# LAD_1_1.net
KiCad netlist of a schematic drawn in EAGLE
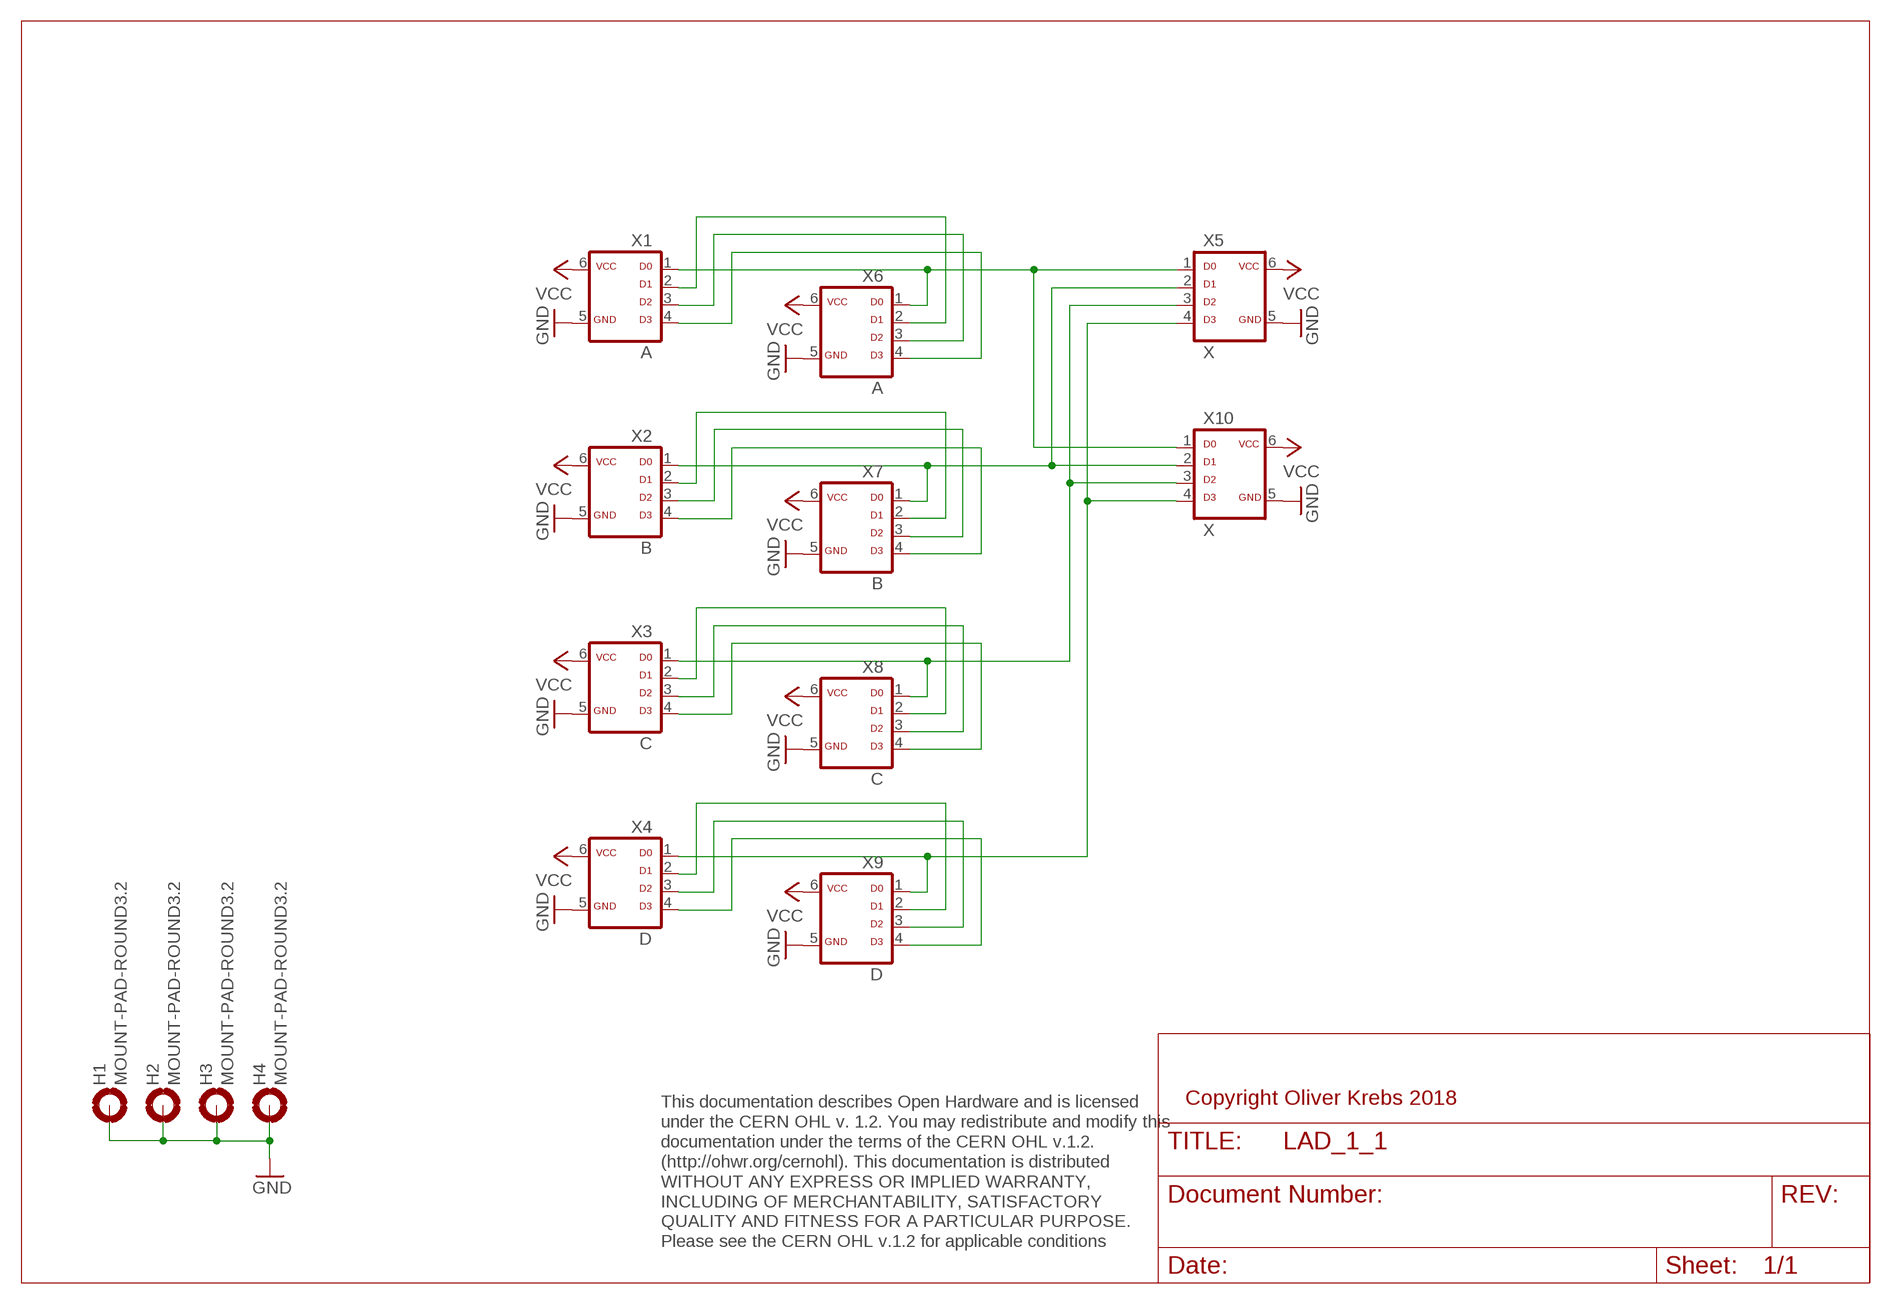
[diagram p0: schematic, sheet 1]

(export (version "E")
  (design (tool "Eeschema 10.0.6"))
  (components
    (comp (ref "H1")
      (value "MOUNT-PAD-ROUND3.2")
      (footprint "eagle-import:3,2-PAD")
      (libsource (lib "eagle-import") (part "MOUNT-PAD-ROUND3.2"))
    )
    (comp (ref "H2")
      (value "MOUNT-PAD-ROUND3.2")
      (footprint "eagle-import:3,2-PAD")
      (libsource (lib "eagle-import") (part "MOUNT-PAD-ROUND3.2"))
    )
    (comp (ref "H3")
      (value "MOUNT-PAD-ROUND3.2")
      (footprint "eagle-import:3,2-PAD")
      (libsource (lib "eagle-import") (part "MOUNT-PAD-ROUND3.2"))
    )
    (comp (ref "H4")
      (value "MOUNT-PAD-ROUND3.2")
      (footprint "eagle-import:3,2-PAD")
      (libsource (lib "eagle-import") (part "MOUNT-PAD-ROUND3.2"))
    )
    (comp (ref "X1")
      (value "A")
      (footprint "eagle-import:ML-6")
      (libsource (lib "eagle-import") (part "ML6D"))
    )
    (comp (ref "X2")
      (value "B")
      (footprint "eagle-import:ML-6")
      (libsource (lib "eagle-import") (part "ML6D"))
    )
    (comp (ref "X3")
      (value "C")
      (footprint "eagle-import:ML-6")
      (libsource (lib "eagle-import") (part "ML6D"))
    )
    (comp (ref "X4")
      (value "D")
      (footprint "eagle-import:ML-6")
      (libsource (lib "eagle-import") (part "ML6D"))
    )
    (comp (ref "X5")
      (value "X")
      (footprint "eagle-import:ML-6")
      (libsource (lib "eagle-import") (part "ML6D"))
    )
    (comp (ref "X6")
      (value "A")
      (footprint "eagle-import:ML-6")
      (libsource (lib "eagle-import") (part "ML6D"))
    )
    (comp (ref "X7")
      (value "B")
      (footprint "eagle-import:ML-6")
      (libsource (lib "eagle-import") (part "ML6D"))
    )
    (comp (ref "X8")
      (value "C")
      (footprint "eagle-import:ML-6")
      (libsource (lib "eagle-import") (part "ML6D"))
    )
    (comp (ref "X9")
      (value "D")
      (footprint "eagle-import:ML-6")
      (libsource (lib "eagle-import") (part "ML6D"))
    )
    (comp (ref "X10")
      (value "X")
      (footprint "eagle-import:ML-6")
      (libsource (lib "eagle-import") (part "ML6D"))
    )
  )
  (nets
    (net (code "1") (name "GND") (class "Default")
      (node (ref "H1") (pin "B3,2") (pinfunction "MOUNT_B3,2") (pintype "passive"))
      (node (ref "H2") (pin "B3,2") (pinfunction "MOUNT_B3,2") (pintype "passive"))
      (node (ref "H3") (pin "B3,2") (pinfunction "MOUNT_B3,2") (pintype "passive"))
      (node (ref "H4") (pin "B3,2") (pinfunction "MOUNT_B3,2") (pintype "passive"))
      (node (ref "X1") (pin "5") (pinfunction "5_5") (pintype "passive"))
      (node (ref "X10") (pin "5") (pinfunction "5_5") (pintype "passive"))
      (node (ref "X2") (pin "5") (pinfunction "5_5") (pintype "passive"))
      (node (ref "X3") (pin "5") (pinfunction "5_5") (pintype "passive"))
      (node (ref "X4") (pin "5") (pinfunction "5_5") (pintype "passive"))
      (node (ref "X5") (pin "5") (pinfunction "5_5") (pintype "passive"))
      (node (ref "X6") (pin "5") (pinfunction "5_5") (pintype "passive"))
      (node (ref "X7") (pin "5") (pinfunction "5_5") (pintype "passive"))
      (node (ref "X8") (pin "5") (pinfunction "5_5") (pintype "passive"))
      (node (ref "X9") (pin "5") (pinfunction "5_5") (pintype "passive"))
    )
    (net (code "2") (name "Net-(X1-Pad1)") (class "Default")
      (node (ref "X1") (pin "1") (pinfunction "1_1") (pintype "passive"))
      (node (ref "X10") (pin "1") (pinfunction "1_1") (pintype "passive"))
      (node (ref "X5") (pin "1") (pinfunction "1_1") (pintype "passive"))
      (node (ref "X6") (pin "1") (pinfunction "1_1") (pintype "passive"))
    )
    (net (code "3") (name "Net-(X1-Pad2)") (class "Default")
      (node (ref "X1") (pin "2") (pinfunction "2_2") (pintype "passive"))
      (node (ref "X6") (pin "2") (pinfunction "2_2") (pintype "passive"))
    )
    (net (code "4") (name "Net-(X1-Pad3)") (class "Default")
      (node (ref "X1") (pin "3") (pinfunction "3_3") (pintype "passive"))
      (node (ref "X6") (pin "3") (pinfunction "3_3") (pintype "passive"))
    )
    (net (code "5") (name "Net-(X1-Pad4)") (class "Default")
      (node (ref "X1") (pin "4") (pinfunction "4_4") (pintype "passive"))
      (node (ref "X6") (pin "4") (pinfunction "4_4") (pintype "passive"))
    )
    (net (code "6") (name "Net-(X2-Pad2)") (class "Default")
      (node (ref "X2") (pin "2") (pinfunction "2_2") (pintype "passive"))
      (node (ref "X7") (pin "2") (pinfunction "2_2") (pintype "passive"))
    )
    (net (code "7") (name "Net-(X2-Pad3)") (class "Default")
      (node (ref "X2") (pin "3") (pinfunction "3_3") (pintype "passive"))
      (node (ref "X7") (pin "3") (pinfunction "3_3") (pintype "passive"))
    )
    (net (code "8") (name "Net-(X2-Pad4)") (class "Default")
      (node (ref "X2") (pin "4") (pinfunction "4_4") (pintype "passive"))
      (node (ref "X7") (pin "4") (pinfunction "4_4") (pintype "passive"))
    )
    (net (code "9") (name "Net-(X3-Pad2)") (class "Default")
      (node (ref "X3") (pin "2") (pinfunction "2_2") (pintype "passive"))
      (node (ref "X8") (pin "2") (pinfunction "2_2") (pintype "passive"))
    )
    (net (code "10") (name "Net-(X3-Pad3)") (class "Default")
      (node (ref "X3") (pin "3") (pinfunction "3_3") (pintype "passive"))
      (node (ref "X8") (pin "3") (pinfunction "3_3") (pintype "passive"))
    )
    (net (code "11") (name "Net-(X3-Pad4)") (class "Default")
      (node (ref "X3") (pin "4") (pinfunction "4_4") (pintype "passive"))
      (node (ref "X8") (pin "4") (pinfunction "4_4") (pintype "passive"))
    )
    (net (code "12") (name "Net-(X4-Pad2)") (class "Default")
      (node (ref "X4") (pin "2") (pinfunction "2_2") (pintype "passive"))
      (node (ref "X9") (pin "2") (pinfunction "2_2") (pintype "passive"))
    )
    (net (code "13") (name "Net-(X4-Pad3)") (class "Default")
      (node (ref "X4") (pin "3") (pinfunction "3_3") (pintype "passive"))
      (node (ref "X9") (pin "3") (pinfunction "3_3") (pintype "passive"))
    )
    (net (code "14") (name "Net-(X4-Pad4)") (class "Default")
      (node (ref "X4") (pin "4") (pinfunction "4_4") (pintype "passive"))
      (node (ref "X9") (pin "4") (pinfunction "4_4") (pintype "passive"))
    )
    (net (code "15") (name "Net-(X10-Pad2)") (class "Default")
      (node (ref "X10") (pin "2") (pinfunction "2_2") (pintype "passive"))
      (node (ref "X2") (pin "1") (pinfunction "1_1") (pintype "passive"))
      (node (ref "X5") (pin "2") (pinfunction "2_2") (pintype "passive"))
      (node (ref "X7") (pin "1") (pinfunction "1_1") (pintype "passive"))
    )
    (net (code "16") (name "Net-(X10-Pad3)") (class "Default")
      (node (ref "X10") (pin "3") (pinfunction "3_3") (pintype "passive"))
      (node (ref "X3") (pin "1") (pinfunction "1_1") (pintype "passive"))
      (node (ref "X5") (pin "3") (pinfunction "3_3") (pintype "passive"))
      (node (ref "X8") (pin "1") (pinfunction "1_1") (pintype "passive"))
    )
    (net (code "17") (name "Net-(X10-Pad4)") (class "Default")
      (node (ref "X10") (pin "4") (pinfunction "4_4") (pintype "passive"))
      (node (ref "X4") (pin "1") (pinfunction "1_1") (pintype "passive"))
      (node (ref "X5") (pin "4") (pinfunction "4_4") (pintype "passive"))
      (node (ref "X9") (pin "1") (pinfunction "1_1") (pintype "passive"))
    )
    (net (code "18") (name "VCC") (class "Default")
      (node (ref "X1") (pin "6") (pinfunction "6_6") (pintype "passive"))
      (node (ref "X10") (pin "6") (pinfunction "6_6") (pintype "passive"))
      (node (ref "X2") (pin "6") (pinfunction "6_6") (pintype "passive"))
      (node (ref "X3") (pin "6") (pinfunction "6_6") (pintype "passive"))
      (node (ref "X4") (pin "6") (pinfunction "6_6") (pintype "passive"))
      (node (ref "X5") (pin "6") (pinfunction "6_6") (pintype "passive"))
      (node (ref "X6") (pin "6") (pinfunction "6_6") (pintype "passive"))
      (node (ref "X7") (pin "6") (pinfunction "6_6") (pintype "passive"))
      (node (ref "X8") (pin "6") (pinfunction "6_6") (pintype "passive"))
      (node (ref "X9") (pin "6") (pinfunction "6_6") (pintype "passive"))
    )
  )
)
